# 10_Clock.net
KiCad netlist of a schematic drawn in Altium Designer
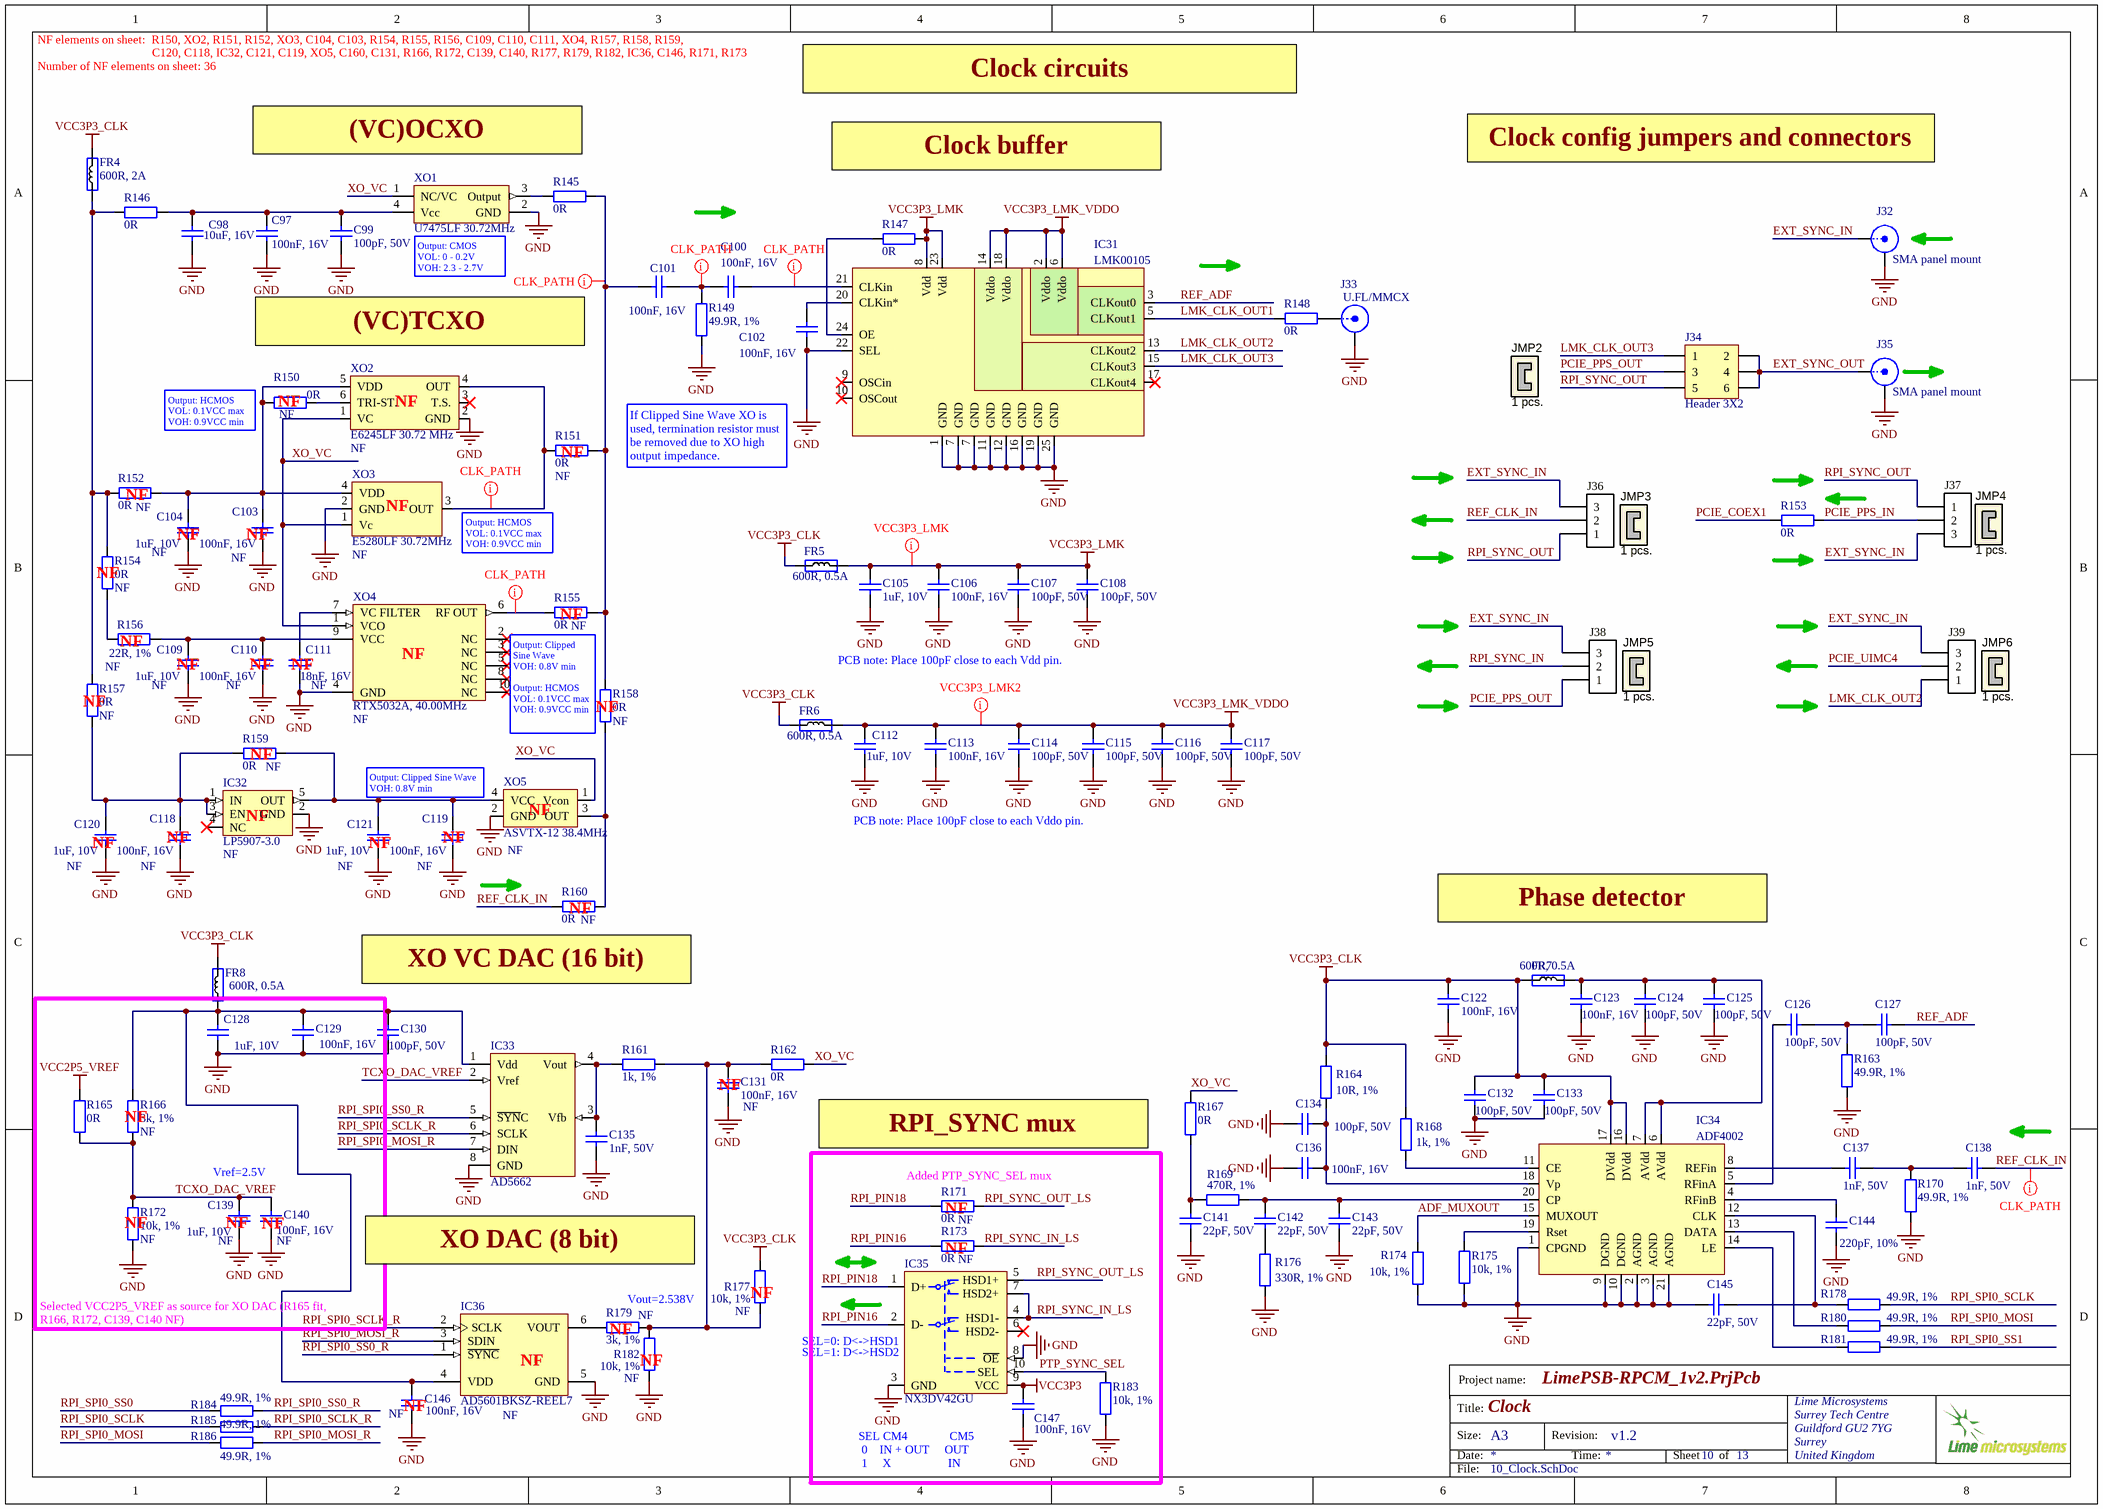
[diagram p0: 10_Clock.SchDoc]

(export (version "E")
  (design (tool "Eeschema 10.0.6"))
  (components
    (comp (ref "C97")
      (value "100nF, 16V")
      (footprint "CAP0402")
      (fields
        (field (name "MANUFACTURER") "Murata Electronics")
        (field (name "TOLERANCE") "10 %")
        (field (name "MANUFACTURER PART NUMBER") "GRM155R71C104KA88D")
      )
      (libsource (lib "LimeMicroAltiumLib_schLib") (part "Cap_0402"))
    )
    (comp (ref "C98")
      (value "10uF, 16V")
      (footprint "CAP0603")
      (fields (field (name "MANUFACTURER") "Yageo") (field (name "TOLERANCE") "±20%"))
      (libsource (lib "LimeMicroAltiumLib_schLib") (part "Cap_0603"))
    )
    (comp (ref "C99")
      (value "100pF, 50V")
      (footprint "CAP0402")
      (fields (field (name "TOLERANCE") "±5%") (field (name "MANUFACTURER") "Yageo"))
      (libsource (lib "LimeMicroAltiumLib_schLib") (part "Cap_0402"))
    )
    (comp (ref "C100")
      (value "100nF, 16V")
      (footprint "CAP0402")
      (fields
        (field (name "MANUFACTURER") "Murata Electronics")
        (field (name "TOLERANCE") "10 %")
        (field (name "MANUFACTURER PART NUMBER") "GRM155R71C104KA88D")
      )
      (libsource (lib "LimeMicroAltiumLib_schLib") (part "Cap_0402"))
    )
    (comp (ref "C101")
      (value "100nF, 16V")
      (footprint "CAP0402")
      (fields
        (field (name "MANUFACTURER") "Murata Electronics")
        (field (name "TOLERANCE") "10 %")
        (field (name "MANUFACTURER PART NUMBER") "GRM155R71C104KA88D")
      )
      (libsource (lib "LimeMicroAltiumLib_schLib") (part "Cap_0402"))
    )
    (comp (ref "C102")
      (value "100nF, 16V")
      (footprint "CAP0402")
      (fields
        (field (name "MANUFACTURER") "Murata Electronics")
        (field (name "TOLERANCE") "10 %")
        (field (name "MANUFACTURER PART NUMBER") "GRM155R71C104KA88D")
      )
      (libsource (lib "LimeMicroAltiumLib_schLib") (part "Cap_0402"))
    )
    (comp (ref "C103")
      (value "100nF, 16V")
      (footprint "CAP0402")
      (fields
        (field (name "ASSEMBLY INFO") "NF")
        (field (name "MANUFACTURER") "Murata Electronics")
        (field (name "TOLERANCE") "10 %")
        (field (name "MANUFACTURER PART NUMBER") "GRM155R71C104KA88D")
      )
      (libsource (lib "LimeMicroAltiumLib_schLib") (part "Cap_0402"))
    )
    (comp (ref "C104")
      (value "1uF, 10V")
      (footprint "CAP0402")
      (description "CAP CER 1UF 10V X5R 0402")
      (fields (field (name "ASSEMBLY INFO") "NF") (field (name "MANUFACTURER") "Yageo"))
      (libsource (lib "LimeMicroAltiumLib_schLib") (part "Cap_0402"))
    )
    (comp (ref "C105")
      (value "1uF, 10V")
      (footprint "CAP0402")
      (description "CAP CER 1UF 10V X5R 0402")
      (fields (field (name "MANUFACTURER") "Yageo") (field (name "TOLERANCE") "±20%"))
      (libsource (lib "LimeMicroAltiumLib_schLib") (part "Cap_0402"))
    )
    (comp (ref "C106")
      (value "100nF, 16V")
      (footprint "CAP0402")
      (fields
        (field (name "MANUFACTURER") "Murata Electronics")
        (field (name "TOLERANCE") "10 %")
        (field (name "MANUFACTURER PART NUMBER") "GRM155R71C104KA88D")
      )
      (libsource (lib "LimeMicroAltiumLib_schLib") (part "Cap_0402"))
    )
    (comp (ref "C107")
      (value "100pF, 50V")
      (footprint "CAP0402")
      (fields (field (name "MANUFACTURER") "Yageo") (field (name "TOLERANCE") "±5%"))
      (libsource (lib "LimeMicroAltiumLib_schLib") (part "Cap_0402"))
    )
    (comp (ref "C108")
      (value "100pF, 50V")
      (footprint "CAP0402")
      (fields (field (name "MANUFACTURER") "Yageo") (field (name "TOLERANCE") "±5%"))
      (libsource (lib "LimeMicroAltiumLib_schLib") (part "Cap_0402"))
    )
    (comp (ref "C109")
      (value "1uF, 10V")
      (footprint "CAP0402")
      (description "CAP CER 1UF 10V X5R 0402")
      (fields (field (name "ASSEMBLY INFO") "NF") (field (name "MANUFACTURER") "Yageo"))
      (libsource (lib "LimeMicroAltiumLib_schLib") (part "Cap_0402"))
    )
    (comp (ref "C110")
      (value "100nF, 16V")
      (footprint "CAP0402")
      (fields
        (field (name "ASSEMBLY INFO") "NF")
        (field (name "MANUFACTURER") "Murata Electronics")
        (field (name "TOLERANCE") "10 %")
        (field (name "MANUFACTURER PART NUMBER") "GRM155R71C104KA88D")
      )
      (libsource (lib "LimeMicroAltiumLib_schLib") (part "Cap_0402"))
    )
    (comp (ref "C111")
      (value "18nF, 16V")
      (footprint "CAP0402")
      (fields
        (field (name "ASSEMBLY INFO") "NF")
        (field (name "MANUFACTURER") "Yageo")
        (field (name "TOLERANCE") "±10%")
      )
      (libsource (lib "LimeMicroAltiumLib_schLib") (part "Cap_0402"))
    )
    (comp (ref "C112")
      (value "1uF, 10V")
      (footprint "CAP0402")
      (description "CAP CER 1UF 10V X5R 0402")
      (fields (field (name "MANUFACTURER") "Yageo") (field (name "TOLERANCE") "±20%"))
      (libsource (lib "LimeMicroAltiumLib_schLib") (part "Cap_0402"))
    )
    (comp (ref "C113")
      (value "100nF, 16V")
      (footprint "CAP0402")
      (fields
        (field (name "MANUFACTURER") "Murata Electronics")
        (field (name "TOLERANCE") "10 %")
        (field (name "MANUFACTURER PART NUMBER") "GRM155R71C104KA88D")
      )
      (libsource (lib "LimeMicroAltiumLib_schLib") (part "Cap_0402"))
    )
    (comp (ref "C114")
      (value "100pF, 50V")
      (footprint "CAP0402")
      (fields (field (name "MANUFACTURER") "Yageo") (field (name "TOLERANCE") "±5%"))
      (libsource (lib "LimeMicroAltiumLib_schLib") (part "Cap_0402"))
    )
    (comp (ref "C115")
      (value "100pF, 50V")
      (footprint "CAP0402")
      (fields (field (name "MANUFACTURER") "Yageo") (field (name "TOLERANCE") "±5%"))
      (libsource (lib "LimeMicroAltiumLib_schLib") (part "Cap_0402"))
    )
    (comp (ref "C116")
      (value "100pF, 50V")
      (footprint "CAP0402")
      (fields (field (name "MANUFACTURER") "Yageo") (field (name "TOLERANCE") "±5%"))
      (libsource (lib "LimeMicroAltiumLib_schLib") (part "Cap_0402"))
    )
    (comp (ref "C117")
      (value "100pF, 50V")
      (footprint "CAP0402")
      (fields (field (name "MANUFACTURER") "Yageo") (field (name "TOLERANCE") "±5%"))
      (libsource (lib "LimeMicroAltiumLib_schLib") (part "Cap_0402"))
    )
    (comp (ref "C118")
      (value "100nF, 16V")
      (footprint "CAP0402")
      (fields
        (field (name "ASSEMBLY INFO") "NF")
        (field (name "MANUFACTURER") "Murata Electronics")
        (field (name "TOLERANCE") "10 %")
        (field (name "MANUFACTURER PART NUMBER") "GRM155R71C104KA88D")
      )
      (libsource (lib "") (part "Cap_0402_1"))
    )
    (comp (ref "C119")
      (value "100nF, 16V")
      (footprint "CAP0402")
      (fields
        (field (name "ASSEMBLY INFO") "NF")
        (field (name "MANUFACTURER") "Murata Electronics")
        (field (name "TOLERANCE") "10 %")
        (field (name "MANUFACTURER PART NUMBER") "GRM155R71C104KA88D")
      )
      (libsource (lib "") (part "Cap_0402_1"))
    )
    (comp (ref "C120")
      (value "1uF, 10V")
      (footprint "CAP0402")
      (fields (field (name "ASSEMBLY INFO") "NF") (field (name "MANUFACTURER") "Yageo"))
      (libsource (lib "") (part "Cap_0402_1"))
    )
    (comp (ref "C121")
      (value "1uF, 10V")
      (footprint "CAP0402")
      (fields (field (name "ASSEMBLY INFO") "NF") (field (name "MANUFACTURER") "Yageo"))
      (libsource (lib "") (part "Cap_0402_1"))
    )
    (comp (ref "C122")
      (value "100nF, 16V")
      (footprint "CAP0402")
      (fields
        (field (name "MANUFACTURER") "Murata Electronics")
        (field (name "TOLERANCE") "10 %")
        (field (name "MANUFACTURER PART NUMBER") "GRM155R71C104KA88D")
      )
      (libsource (lib "LimeMicroAltiumLib_schLib") (part "Cap_0402"))
    )
    (comp (ref "C123")
      (value "100nF, 16V")
      (footprint "CAP0402")
      (fields
        (field (name "MANUFACTURER") "Murata Electronics")
        (field (name "TOLERANCE") "10 %")
        (field (name "MANUFACTURER PART NUMBER") "GRM155R71C104KA88D")
      )
      (libsource (lib "LimeMicroAltiumLib_schLib") (part "Cap_0402"))
    )
    (comp (ref "C124")
      (value "100pF, 50V")
      (footprint "CAP0402")
      (fields (field (name "MANUFACTURER") "Yageo") (field (name "TOLERANCE") "±5%"))
      (libsource (lib "LimeMicroAltiumLib_schLib") (part "Cap_0402"))
    )
    (comp (ref "C125")
      (value "100pF, 50V")
      (footprint "CAP0402")
      (fields (field (name "MANUFACTURER") "Yageo") (field (name "TOLERANCE") "±5%"))
      (libsource (lib "LimeMicroAltiumLib_schLib") (part "Cap_0402"))
    )
    (comp (ref "C126")
      (value "100pF, 50V")
      (footprint "CAP0402")
      (fields (field (name "MANUFACTURER") "Yageo") (field (name "TOLERANCE") "±5%"))
      (libsource (lib "LimeMicroAltiumLib_schLib") (part "Cap_0402"))
    )
    (comp (ref "C127")
      (value "100pF, 50V")
      (footprint "CAP0402")
      (fields (field (name "MANUFACTURER") "Yageo") (field (name "TOLERANCE") "±5%"))
      (libsource (lib "LimeMicroAltiumLib_schLib") (part "Cap_0402"))
    )
    (comp (ref "C128")
      (value "1uF, 10V")
      (footprint "CAP0402")
      (description "CAP CER 1UF 10V X5R 0402")
      (fields (field (name "MANUFACTURER") "Yageo") (field (name "TOLERANCE") "±20%"))
      (libsource (lib "LimeMicroAltiumLib_schLib") (part "Cap_0402"))
    )
    (comp (ref "C129")
      (value "100nF, 16V")
      (footprint "CAP0402")
      (fields
        (field (name "TOLERANCE") "10 %")
        (field (name "MANUFACTURER") "Murata Electronics")
        (field (name "MANUFACTURER PART NUMBER") "GRM155R71C104KA88D")
      )
      (libsource (lib "LimeFPGAboard_schLib") (part "Cap_0603"))
    )
    (comp (ref "C130")
      (value "100pF, 50V")
      (footprint "CAP0402")
      (fields (field (name "MANUFACTURER") "Yageo") (field (name "TOLERANCE") "±5%"))
      (libsource (lib "LimeMicroAltiumLib_schLib") (part "Cap_0402"))
    )
    (comp (ref "C131")
      (value "100nF, 16V")
      (footprint "CAP0402")
      (fields
        (field (name "ASSEMBLY INFO") "NF")
        (field (name "MANUFACTURER") "Murata Electronics")
        (field (name "TOLERANCE") "10 %")
        (field (name "MANUFACTURER PART NUMBER") "GRM155R71C104KA88D")
      )
      (libsource (lib "LimeMicroAltiumLib_schLib") (part "Cap_0402"))
    )
    (comp (ref "C132")
      (value "100pF, 50V")
      (footprint "CAP0402")
      (fields (field (name "MANUFACTURER") "Yageo") (field (name "TOLERANCE") "±5%"))
      (libsource (lib "LimeMicroAltiumLib_schLib") (part "Cap_0402"))
    )
    (comp (ref "C133")
      (value "100pF, 50V")
      (footprint "CAP0402")
      (fields (field (name "MANUFACTURER") "Yageo") (field (name "TOLERANCE") "±5%"))
      (libsource (lib "LimeMicroAltiumLib_schLib") (part "Cap_0402"))
    )
    (comp (ref "C134")
      (value "100pF, 50V")
      (footprint "CAP0402")
      (fields (field (name "MANUFACTURER") "Yageo") (field (name "TOLERANCE") "±5%"))
      (libsource (lib "LimeMicroAltiumLib_schLib") (part "Cap_0402"))
    )
    (comp (ref "C135")
      (value "1nF, 50V")
      (footprint "CAP0402")
      (fields
        (field (name "TOLERANCE") "±10%")
        (field (name "MANUFACTURER") "Murata Electronics North America")
      )
      (libsource (lib "LimeMicroAltiumLib_schLib") (part "Cap_0402"))
    )
    (comp (ref "C136")
      (value "100nF, 16V")
      (footprint "CAP0402")
      (fields
        (field (name "MANUFACTURER") "Murata Electronics")
        (field (name "TOLERANCE") "10 %")
        (field (name "MANUFACTURER PART NUMBER") "GRM155R71C104KA88D")
      )
      (libsource (lib "LimeMicroAltiumLib_schLib") (part "Cap_0402"))
    )
    (comp (ref "C137")
      (value "1nF, 50V")
      (footprint "CAP0402")
      (fields
        (field (name "TOLERANCE") "±10%")
        (field (name "MANUFACTURER") "Murata Electronics North America")
      )
      (libsource (lib "LimeMicroAltiumLib_schLib") (part "Cap_0402"))
    )
    (comp (ref "C138")
      (value "1nF, 50V")
      (footprint "CAP0402")
      (fields
        (field (name "TOLERANCE") "±10%")
        (field (name "MANUFACTURER") "Murata Electronics North America")
      )
      (libsource (lib "LimeMicroAltiumLib_schLib") (part "Cap_0402"))
    )
    (comp (ref "C139")
      (value "1uF, 10V")
      (footprint "CAP0402")
      (description "CAP CER 1UF 10V X5R 0402")
      (fields
        (field (name "ASSEMBLY INFO") "NF")
        (field (name "MANUFACTURER") "Yageo")
        (field (name "TOLERANCE") "±20%")
      )
      (libsource (lib "LimeMicroAltiumLib_schLib") (part "Cap_0402"))
    )
    (comp (ref "C140")
      (value "100nF, 16V")
      (footprint "CAP0402")
      (fields
        (field (name "TOLERANCE") "10 %")
        (field (name "MANUFACTURER") "Murata Electronics")
        (field (name "MANUFACTURER PART NUMBER") "GRM155R71C104KA88D")
        (field (name "ASSEMBLY INFO") "NF")
      )
      (libsource (lib "LimeFPGAboard_schLib") (part "Cap_0603"))
    )
    (comp (ref "C141")
      (value "22pF, 50V")
      (footprint "CAP0402")
      (fields (field (name "TOLERANCE") "±5%") (field (name "MANUFACTURER") "Yageo"))
      (libsource (lib "LimeMicroAltiumLib_schLib") (part "Cap_0402"))
    )
    (comp (ref "C142")
      (value "22pF, 50V")
      (footprint "CAP0402")
      (fields (field (name "TOLERANCE") "±5%") (field (name "MANUFACTURER") "Yageo"))
      (libsource (lib "LimeMicroAltiumLib_schLib") (part "Cap_0402"))
    )
    (comp (ref "C143")
      (value "22pF, 50V")
      (footprint "CAP0402")
      (fields (field (name "TOLERANCE") "±5%") (field (name "MANUFACTURER") "Yageo"))
      (libsource (lib "LimeMicroAltiumLib_schLib") (part "Cap_0402"))
    )
    (comp (ref "C144")
      (value "220pF, 10%")
      (footprint "CAP0402")
      (fields (field (name "MANUFACTURER") "Yageo") (field (name "TOLERANCE") "±10%"))
      (libsource (lib "LimeMicroAltiumLib_schLib") (part "Cap_0402"))
    )
    (comp (ref "C145")
      (value "22pF, 50V")
      (footprint "CAP0402")
      (fields (field (name "TOLERANCE") "±5%") (field (name "MANUFACTURER") "Yageo"))
      (libsource (lib "LimeMicroAltiumLib_schLib") (part "Cap_0402"))
    )
    (comp (ref "C146")
      (value "100nF, 16V")
      (footprint "CAP0402")
      (fields
        (field (name "TOLERANCE") "10 %")
        (field (name "MANUFACTURER") "Murata Electronics")
        (field (name "MANUFACTURER PART NUMBER") "GRM155R71C104KA88D")
        (field (name "ASSEMBLY INFO") "NF")
      )
      (libsource (lib "LimeFPGAboard_schLib") (part "Cap_0603"))
    )
    (comp (ref "C147")
      (value "100nF, 16V")
      (footprint "CAP0402")
      (fields
        (field (name "MANUFACTURER") "Murata Electronics")
        (field (name "TOLERANCE") "10 %")
        (field (name "MANUFACTURER PART NUMBER") "GRM155R71C104KA88D")
      )
      (libsource (lib "LimeMicroAltiumLib_schLib") (part "Cap_0402"))
    )
    (comp (ref "FR4")
      (value "600R, 2A")
      (footprint "RES0805")
      (fields (field (name "MANUFACTURER") "TDK Corporation"))
      (libsource (lib "LimeFPGAboard_schLib") (part "Ferrite"))
    )
    (comp (ref "FR5")
      (value "600R, 0.5A")
      (footprint "RES0402")
      (fields (field (name "MANUFACTURER") "Murata") (field (name "TOLERANCE") "25%"))
      (libsource (lib "LimeMicroAltiumLib_schLib") (part "Ferrite"))
    )
    (comp (ref "FR6")
      (value "600R, 0.5A")
      (footprint "RES0402")
      (fields (field (name "MANUFACTURER") "Murata") (field (name "TOLERANCE") "25%"))
      (libsource (lib "LimeMicroAltiumLib_schLib") (part "Ferrite"))
    )
    (comp (ref "FR7")
      (value "600R, 0.5A")
      (footprint "RES0402")
      (fields (field (name "MANUFACTURER") "Murata") (field (name "TOLERANCE") "25%"))
      (libsource (lib "LimeMicroAltiumLib_schLib") (part "Ferrite"))
    )
    (comp (ref "FR8")
      (value "600R, 0.5A")
      (footprint "RES0402")
      (fields (field (name "MANUFACTURER") "Murata") (field (name "TOLERANCE") "25%"))
      (libsource (lib "LimeMicroAltiumLib_schLib") (part "Ferrite"))
    )
    (comp (ref "IC31")
      (value "LMK00105")
      (footprint "LMK00105SQ")
      (fields (field (name "MANUFACTURER") "Texas Instruments"))
      (libsource (lib "LimeMicroAltiumLib_schLib") (part "LMK00105"))
    )
    (comp (ref "IC32")
      (value "LP5907-3.0")
      (footprint "SOT23-5")
      (fields (field (name "MANUFACTURER") "Texas Instruments") (field (name "ASSEMBLY INFO") "NF"))
      (libsource (lib "LimeMicroAltiumLib_schLib_r01") (part "LP5907"))
    )
    (comp (ref "IC33")
      (value "AD5662")
      (footprint "AD5662_SOT23-8")
      (fields (field (name "MANUFACTURER") "Analog Devices Inc."))
      (libsource (lib "LimeMicroAltiumLib_schLib") (part "AD5662"))
    )
    (comp (ref "IC34")
      (value "ADF4002")
      (footprint "ADF4002")
      (fields (field (name "MANUFACTURER") "Analog Devices Inc"))
      (libsource (lib "LimeMicroAltiumLib_schLib") (part "ADF4002"))
    )
    (comp (ref "IC35")
      (value "NX3DV42GU")
      (footprint "FSUSB42UMX")
      (fields (field (name "MANUFACTURER") "NXP Semiconductors"))
      (libsource (lib "LimeMicroAltiumLib_schLib_r01") (part "FSUSB42UMX"))
    )
    (comp (ref "IC36")
      (value "AD5601BKSZ-REEL7")
      (footprint "AD5601_SOT23-6")
      (fields
        (field (name "GENERIC PART NUMBER") "AD5601")
        (field (name "MANUFACTURER") "Analog Devices")
        (field (name "ASSEMBLY INFO") "NF")
      )
      (libsource (lib "LimeMicroAltiumLib_schLib") (part "AD5601BKSZ-REEL7"))
    )
    (comp (ref "J32")
      (value "SMA panel mount")
      (footprint "SMA_connector_side")
      (description "CONN SMA JACK STR 50OHM EDGE MNT")
      (fields (field (name "MANUFACTURER") "Linx"))
      (libsource (lib "") (part "RF_IF_connector_1"))
    )
    (comp (ref "J33")
      (value "U.FL/MMCX")
      (footprint "MMCX_UFL_conn_u")
      (description "CONN UMC RCPT STR 50 OHM SMD")
      (fields (field (name "MANUFACTURER") "Molex, LLC"))
      (libsource (lib "LimeMicroAltiumLib_schLib") (part "RF_IF_connector"))
    )
    (comp (ref "J34")
      (value "Header 3X2")
      (footprint "Header3x2")
      (description "Header, 2-Pin, Dual row")
      (fields
        (field (name "MANUFACTURER PART NUMBER") "PH2-06-UA")
        (field (name "MANUFACTURER") "Adam Equipment")
      )
      (libsource (lib "LimeMicroAltiumLib_schLib_r01") (part "Header 3X2"))
    )
    (comp (ref "J35")
      (value "SMA panel mount")
      (footprint "SMA_connector_side")
      (description "CONN SMA JACK STR 50OHM EDGE MNT")
      (fields (field (name "MANUFACTURER") "Linx"))
      (libsource (lib "") (part "RF_IF_connector_1"))
    )
    (comp (ref "J36")
      (value "Header 3x1 pin")
      (footprint "HDR_1x3")
      (description "Header, 3-pin")
      (fields
        (field (name "MANUFACTURER PART NUMBER") "61300311121")
        (field (name "MANUFACTURER") "Wurth Electronics")
      )
      (libsource (lib "LimeMicroAltiumLib_schLib_r04") (part "Header3P"))
    )
    (comp (ref "J37")
      (value "Header 3x1 pin")
      (footprint "HDR_1x3")
      (description "Header, 3-pin")
      (fields
        (field (name "MANUFACTURER PART NUMBER") "61300311121")
        (field (name "MANUFACTURER") "Wurth Electronics")
      )
      (libsource (lib "") (part "Header3P_1"))
    )
    (comp (ref "J38")
      (value "Header 3x1 pin")
      (footprint "HDR_1x3")
      (description "Header, 3-pin")
      (fields
        (field (name "MANUFACTURER PART NUMBER") "61300311121")
        (field (name "MANUFACTURER") "Wurth Electronics")
      )
      (libsource (lib "LimeMicroAltiumLib_schLib_r04") (part "Header3P"))
    )
    (comp (ref "J39")
      (value "Header 3x1 pin")
      (footprint "HDR_1x3")
      (description "Header, 3-pin")
      (fields
        (field (name "MANUFACTURER PART NUMBER") "61300311121")
        (field (name "MANUFACTURER") "Wurth Electronics")
      )
      (libsource (lib "LimeMicroAltiumLib_schLib_r04") (part "Header3P"))
    )
    (comp (ref "JMP2")
      (value "1 pcs.")
      (description "Shorting Jumper, 2-position, 1.27mm pitch")
      (fields (field (name "MANUFACTURER") "Sullins"))
      (libsource (lib "LimeMicroAltiumLib_schLib") (part "JUMP_2P_CONN_HEADER"))
    )
    (comp (ref "JMP3")
      (value "1 pcs.")
      (description "Shorting Jumper, 2-position, 1.27mm pitch")
      (fields (field (name "MANUFACTURER") "Sullins"))
      (libsource (lib "LimeMicroAltiumLib_schLib") (part "JUMP_2P_CONN_HEADER"))
    )
    (comp (ref "JMP4")
      (value "1 pcs.")
      (description "Shorting Jumper, 2-position, 1.27mm pitch")
      (fields (field (name "MANUFACTURER") "Sullins"))
      (libsource (lib "LimeMicroAltiumLib_schLib") (part "JUMP_2P_CONN_HEADER"))
    )
    (comp (ref "JMP5")
      (value "1 pcs.")
      (description "Shorting Jumper, 2-position, 1.27mm pitch")
      (fields (field (name "MANUFACTURER") "Sullins"))
      (libsource (lib "LimeMicroAltiumLib_schLib") (part "JUMP_2P_CONN_HEADER"))
    )
    (comp (ref "JMP6")
      (value "1 pcs.")
      (description "Shorting Jumper, 2-position, 1.27mm pitch")
      (fields (field (name "MANUFACTURER") "Sullins"))
      (libsource (lib "LimeMicroAltiumLib_schLib") (part "JUMP_2P_CONN_HEADER"))
    )
    (comp (ref "R145")
      (value "0R")
      (footprint "RES0402_v2")
      (fields (field (name "MANUFACTURER") "Yageo") (field (name "TOLERANCE") "Jumper"))
      (libsource (lib "LimeMicroAltiumLib_schLib") (part "Res_0402"))
    )
    (comp (ref "R146")
      (value "0R")
      (footprint "RES0402")
      (fields (field (name "MANUFACTURER") "Yageo") (field (name "TOLERANCE") "Jumper"))
      (libsource (lib "LimeMicroAltiumLib_schLib") (part "Res_0402"))
    )
    (comp (ref "R147")
      (value "0R")
      (footprint "RES0402")
      (fields (field (name "MANUFACTURER") "Yageo") (field (name "TOLERANCE") "Jumper"))
      (libsource (lib "LimeMicroAltiumLib_schLib") (part "Res_0402"))
    )
    (comp (ref "R148")
      (value "0R")
      (footprint "RES0402")
      (fields (field (name "MANUFACTURER") "Yageo") (field (name "TOLERANCE") "Jumper"))
      (libsource (lib "") (part "Res_0402_1"))
    )
    (comp (ref "R149")
      (value "49.9R, 1%")
      (footprint "RES0402")
      (fields
        (field (name "TOLERANCE") "±1%")
        (field (name "MANUFACTURER") "Samsung Electro-Mechanics America, Inc.")
      )
      (libsource (lib "LimeMicroAltiumLib_schLib") (part "Res_0402"))
    )
    (comp (ref "R150")
      (value "0R")
      (footprint "RES0402")
      (fields
        (field (name "ASSEMBLY INFO") "NF")
        (field (name "MANUFACTURER") "Yageo")
        (field (name "TOLERANCE") "Jumper")
      )
      (libsource (lib "LimeMicroAltiumLib_schLib") (part "Res_0402"))
    )
    (comp (ref "R151")
      (value "0R")
      (footprint "RES0402_v2")
      (fields
        (field (name "ASSEMBLY INFO") "NF")
        (field (name "MANUFACTURER") "Yageo")
        (field (name "TOLERANCE") "Jumper")
      )
      (libsource (lib "LimeMicroAltiumLib_schLib") (part "Res_0402"))
    )
    (comp (ref "R152")
      (value "0R")
      (footprint "RES0402")
      (fields
        (field (name "MANUFACTURER") "Yageo")
        (field (name "TOLERANCE") "Jumper")
        (field (name "ASSEMBLY INFO") "NF")
      )
      (libsource (lib "LimeMicroAltiumLib_schLib") (part "Res_0402"))
    )
    (comp (ref "R153")
      (value "0R")
      (footprint "RES0402")
      (fields (field (name "MANUFACTURER") "Yageo") (field (name "TOLERANCE") "Jumper"))
      (libsource (lib "") (part "Res_0402_1"))
    )
    (comp (ref "R154")
      (value "0R")
      (footprint "RES0402")
      (fields
        (field (name "ASSEMBLY INFO") "NF")
        (field (name "MANUFACTURER") "Yageo")
        (field (name "TOLERANCE") "Jumper")
      )
      (libsource (lib "LimeMicroAltiumLib_schLib") (part "Res_0402"))
    )
    (comp (ref "R155")
      (value "0R")
      (footprint "RES0402_v2")
      (fields
        (field (name "ASSEMBLY INFO") "NF")
        (field (name "MANUFACTURER") "Yageo")
        (field (name "TOLERANCE") "Jumper")
      )
      (libsource (lib "LimeMicroAltiumLib_schLib") (part "Res_0402"))
    )
    (comp (ref "R156")
      (value "22R, 1%")
      (footprint "RES0402")
      (fields
        (field (name "TOLERANCE") "±1%")
        (field (name "MANUFACTURER") "Yageo")
        (field (name "ASSEMBLY INFO") "NF")
      )
      (libsource (lib "LimeFPGAboard_schLib") (part "Res_0402"))
    )
    (comp (ref "R157")
      (value "0R")
      (footprint "RES0402")
      (fields
        (field (name "MANUFACTURER") "Yageo")
        (field (name "TOLERANCE") "Jumper")
        (field (name "ASSEMBLY INFO") "NF")
      )
      (libsource (lib "") (part "Res_0402_1"))
    )
    (comp (ref "R158")
      (value "0R")
      (footprint "RES0402_v2")
      (fields
        (field (name "ASSEMBLY INFO") "NF")
        (field (name "MANUFACTURER") "Yageo")
        (field (name "TOLERANCE") "Jumper")
      )
      (libsource (lib "") (part "Res_0402_1"))
    )
    (comp (ref "R159")
      (value "0R")
      (footprint "RES0402")
      (fields
        (field (name "MANUFACTURER") "Yageo")
        (field (name "TOLERANCE") "Jumper")
        (field (name "ASSEMBLY INFO") "NF")
      )
      (libsource (lib "") (part "Res_0402_1"))
    )
    (comp (ref "R160")
      (value "0R")
      (footprint "RES0402_v2")
      (fields
        (field (name "ASSEMBLY INFO") "NF")
        (field (name "MANUFACTURER") "Yageo")
        (field (name "TOLERANCE") "Jumper")
      )
      (libsource (lib "LimeMicroAltiumLib_schLib") (part "Res_0402"))
    )
    (comp (ref "R161")
      (value "1k, 1%")
      (footprint "RES0402")
      (fields (field (name "MANUFACTURER") "Stackpole Electronics Inc") (field (name "TOLERANCE") "±1%"))
      (libsource (lib "LimeMicroAltiumLib_schLib") (part "Res_0402"))
    )
    (comp (ref "R162")
      (value "0R")
      (footprint "RES0402")
      (fields (field (name "MANUFACTURER") "Yageo") (field (name "TOLERANCE") "Jumper"))
      (libsource (lib "LimeMicroAltiumLib_schLib") (part "Res_0402"))
    )
    (comp (ref "R163")
      (value "49.9R, 1%")
      (footprint "RES0402")
      (fields
        (field (name "TOLERANCE") "±1%")
        (field (name "MANUFACTURER") "Samsung Electro-Mechanics America, Inc.")
      )
      (libsource (lib "LimeMicroAltiumLib_schLib") (part "Res_0402"))
    )
    (comp (ref "R164")
      (value "10R, 1%")
      (footprint "RES0402")
      (fields (field (name "MANUFACTURER") "Stackpole Electronics") (field (name "TOLERANCE") "1%"))
      (libsource (lib "LimeMicroAltiumLib_schLib") (part "Res_0402"))
    )
    (comp (ref "R165")
      (value "0R")
      (footprint "RES0402_v2")
      (fields (field (name "MANUFACTURER") "Yageo") (field (name "TOLERANCE") "Jumper"))
      (libsource (lib "LimeMicroAltiumLib_schLib") (part "Res_0402"))
    )
    (comp (ref "R166")
      (value "3k, 1%")
      (footprint "RES0402")
      (fields
        (field (name "ASSEMBLY INFO") "NF")
        (field (name "TOLERANCE") "±1%")
        (field (name "MANUFACTURER") "Vishay Dale")
      )
      (libsource (lib "LimeMicroAltiumLib_schLib") (part "Res_0402"))
    )
    (comp (ref "R167")
      (value "0R")
      (footprint "RES0402")
      (fields (field (name "MANUFACTURER") "Yageo") (field (name "TOLERANCE") "Jumper"))
      (libsource (lib "LimeMicroAltiumLib_schLib") (part "Res_0402"))
    )
    (comp (ref "R168")
      (value "1k, 1%")
      (footprint "RES0402")
      (fields (field (name "MANUFACTURER") "Stackpole Electronics Inc") (field (name "TOLERANCE") "±1%"))
      (libsource (lib "LimeMicroAltiumLib_schLib") (part "Res_0402"))
    )
    (comp (ref "R169")
      (value "470R, 1%")
      (footprint "RES0402")
      (fields (field (name "TOLERANCE") "1%") (field (name "MANUFACTURER") "Yageo"))
      (libsource (lib "") (part "Res_0402_1"))
    )
    (comp (ref "R170")
      (value "49.9R, 1%")
      (footprint "RES0402")
      (fields
        (field (name "TOLERANCE") "±1%")
        (field (name "MANUFACTURER") "Samsung Electro-Mechanics America, Inc.")
      )
      (libsource (lib "LimeMicroAltiumLib_schLib") (part "Res_0402"))
    )
    (comp (ref "R171")
      (value "0R")
      (footprint "RES0402")
      (fields
        (field (name "ASSEMBLY INFO") "NF")
        (field (name "MANUFACTURER") "Yageo")
        (field (name "TOLERANCE") "Jumper")
      )
      (libsource (lib "") (part "Res_0402_1"))
    )
    (comp (ref "R172")
      (value "10k, 1%")
      (footprint "RES0402")
      (fields
        (field (name "ASSEMBLY INFO") "NF")
        (field (name "MANUFACTURER") "Yageo")
        (field (name "TOLERANCE") "±1%")
      )
      (libsource (lib "LimeMicroAltiumLib_schLib") (part "Res_0402"))
    )
    (comp (ref "R173")
      (value "0R")
      (footprint "RES0402")
      (fields
        (field (name "ASSEMBLY INFO") "NF")
        (field (name "MANUFACTURER") "Yageo")
        (field (name "TOLERANCE") "Jumper")
      )
      (libsource (lib "") (part "Res_0402_1"))
    )
    (comp (ref "R174")
      (value "10k, 1%")
      (footprint "RES0402")
      (fields (field (name "MANUFACTURER") "Yageo") (field (name "TOLERANCE") "±1%"))
      (libsource (lib "LimeMicroAltiumLib_schLib") (part "Res_0402"))
    )
    (comp (ref "R175")
      (value "10k, 1%")
      (footprint "RES0402")
      (fields (field (name "MANUFACTURER") "Yageo") (field (name "TOLERANCE") "±1%"))
      (libsource (lib "LimeMicroAltiumLib_schLib") (part "Res_0402"))
    )
    (comp (ref "R176")
      (value "330R, 1%")
      (footprint "RES0402")
      (fields (field (name "MANUFACTURER") "Yageo") (field (name "TOLERANCE") "1%"))
      (libsource (lib "LimeMicroAltiumLib_schLib") (part "Res_0402"))
    )
    (comp (ref "R177")
      (value "10k, 1%")
      (footprint "RES0402")
      (fields
        (field (name "ASSEMBLY INFO") "NF")
        (field (name "MANUFACTURER") "Yageo")
        (field (name "TOLERANCE") "±1%")
      )
      (libsource (lib "LimeMicroAltiumLib_schLib") (part "Res_0402"))
    )
    (comp (ref "R178")
      (value "49.9R, 1%")
      (footprint "RES0402")
      (fields
        (field (name "TOLERANCE") "±1%")
        (field (name "MANUFACTURER") "Samsung Electro-Mechanics America, Inc.")
      )
      (libsource (lib "LimeMicroAltiumLib_schLib") (part "Res_0402"))
    )
    (comp (ref "R179")
      (value "3k, 1%")
      (footprint "RES0402")
      (fields
        (field (name "ASSEMBLY INFO") "NF")
        (field (name "TOLERANCE") "±1%")
        (field (name "MANUFACTURER") "Vishay Dale")
      )
      (libsource (lib "LimeMicroAltiumLib_schLib") (part "Res_0402"))
    )
    (comp (ref "R180")
      (value "49.9R, 1%")
      (footprint "RES0402")
      (fields
        (field (name "TOLERANCE") "±1%")
        (field (name "MANUFACTURER") "Samsung Electro-Mechanics America, Inc.")
      )
      (libsource (lib "LimeMicroAltiumLib_schLib") (part "Res_0402"))
    )
    (comp (ref "R181")
      (value "49.9R, 1%")
      (footprint "RES0402")
      (fields
        (field (name "TOLERANCE") "±1%")
        (field (name "MANUFACTURER") "Samsung Electro-Mechanics America, Inc.")
      )
      (libsource (lib "LimeMicroAltiumLib_schLib") (part "Res_0402"))
    )
    (comp (ref "R182")
      (value "10k, 1%")
      (footprint "RES0402")
      (fields
        (field (name "ASSEMBLY INFO") "NF")
        (field (name "MANUFACTURER") "Yageo")
        (field (name "TOLERANCE") "±1%")
      )
      (libsource (lib "LimeMicroAltiumLib_schLib") (part "Res_0402"))
    )
    (comp (ref "R183")
      (value "10k, 1%")
      (footprint "RES0402")
      (fields (field (name "MANUFACTURER") "Yageo") (field (name "TOLERANCE") "±1%"))
      (libsource (lib "LimeMicroAltiumLib_schLib") (part "Res_0402"))
    )
    (comp (ref "R184")
      (value "49.9R, 1%")
      (footprint "RES0402")
      (fields
        (field (name "TOLERANCE") "±1%")
        (field (name "MANUFACTURER") "Samsung Electro-Mechanics America, Inc.")
      )
      (libsource (lib "LimeMicroAltiumLib_schLib") (part "Res_0402"))
    )
    (comp (ref "R185")
      (value "49.9R, 1%")
      (footprint "RES0402")
      (fields
        (field (name "TOLERANCE") "±1%")
        (field (name "MANUFACTURER") "Samsung Electro-Mechanics America, Inc.")
      )
      (libsource (lib "LimeMicroAltiumLib_schLib") (part "Res_0402"))
    )
    (comp (ref "R186")
      (value "49.9R, 1%")
      (footprint "RES0402")
      (fields
        (field (name "TOLERANCE") "±1%")
        (field (name "MANUFACTURER") "Samsung Electro-Mechanics America, Inc.")
      )
      (libsource (lib "LimeMicroAltiumLib_schLib") (part "Res_0402"))
    )
    (comp (ref "XO1")
      (value "U7475LF 30.72MHz")
      (footprint "AOCJYR-10.000MHz")
      (fields (field (name "MANUFACTURER") "Rakon"))
      (libsource (lib "LimeMicroAltiumLib_schLib") (part "AOCJYR-10.000MHz"))
    )
    (comp (ref "XO2")
      (value "E6245LF 30.72 MHz")
      (footprint "RAKON_RPT7050A")
      (fields (field (name "ASSEMBLY INFO") "NF") (field (name "MANUFACTURER") "Rakon"))
      (libsource (lib "LimeMicroAltiumLib_schLib") (part "RPT7050A"))
    )
    (comp (ref "XO3")
      (value "E5280LF 30.72MHz")
      (footprint "RAKON_TXCO")
      (fields (field (name "ASSEMBLY INFO") "NF") (field (name "MANUFACTURER") "Rakon"))
      (libsource (lib "LimeMicroAltiumLib_schLib") (part "TXCO"))
    )
    (comp (ref "XO4")
      (value "RTX5032A, 40.00MHz")
      (footprint "RAKON_RTX5032A")
      (fields (field (name "ASSEMBLY INFO") "NF") (field (name "MANUFACTURER") "Rakon"))
      (libsource (lib "LimeMicroAltiumLib_schLib") (part "Rakon_RTX5032A"))
    )
    (comp (ref "XO5")
      (value "ASVTX-12 38.4MHz")
      (footprint "CRYSTAL_4-LCC_2P5x2P0")
      (description "Oscillator Crystal")
      (fields (field (name "MANUFACTURER") "Abracon") (field (name "ASSEMBLY INFO") "NF"))
      (libsource (lib "LimeMicroAltiumLib_schLib_r01") (part "ASVTX-12-A-38.400MHZ-H10-T_CRYSTAL"))
    )
  )
  (nets
    (net (code "1") (name "/ADF_MUXOUT") (class "Default")
      (node (ref "IC34") (pin "15") (pinfunction "MUXOUT_15") (pintype "passive"))
      (node (ref "R174") (pin "1") (pinfunction "1_1") (pintype "passive"))
    )
    (net (code "2") (name "/EXT_SYNC_IN") (class "Default")
      (node (ref "J32") (pin "1") (pinfunction "X_1") (pintype "passive"))
      (node (ref "J36") (pin "3") (pinfunction "3_3") (pintype "passive"))
      (node (ref "J37") (pin "3") (pinfunction "3_3") (pintype "passive"))
      (node (ref "J38") (pin "3") (pinfunction "3_3") (pintype "passive"))
      (node (ref "J39") (pin "3") (pinfunction "3_3") (pintype "passive"))
    )
    (net (code "3") (name "/EXT_SYNC_OUT") (class "Default")
      (node (ref "J34") (pin "2") (pinfunction "2_2") (pintype "passive"))
      (node (ref "J34") (pin "4") (pinfunction "4_4") (pintype "passive"))
      (node (ref "J34") (pin "6") (pinfunction "6_6") (pintype "passive"))
      (node (ref "J35") (pin "1") (pinfunction "X_1") (pintype "passive"))
    )
    (net (code "4") (name "/LMK_CLK_OUT1") (class "Default")
      (node (ref "IC31") (pin "5") (pinfunction "CLKout1_5") (pintype "passive"))
      (node (ref "R148") (pin "2") (pinfunction "2_2") (pintype "passive"))
    )
    (net (code "5") (name "/LMK_CLK_OUT2") (class "Default")
      (node (ref "IC31") (pin "13") (pinfunction "CLKout2_13") (pintype "passive"))
      (node (ref "J39") (pin "1") (pinfunction "1_1") (pintype "passive"))
    )
    (net (code "6") (name "/LMK_CLK_OUT3") (class "Default")
      (node (ref "IC31") (pin "15") (pinfunction "CLKout3_15") (pintype "passive"))
      (node (ref "J34") (pin "1") (pinfunction "1_1") (pintype "passive"))
    )
    (net (code "7") (name "/PCIE_COEX1") (class "Default")
      (node (ref "R153") (pin "2") (pinfunction "2_2") (pintype "passive"))
    )
    (net (code "9") (name "/PCIE_PPS_OUT") (class "Default")
      (node (ref "J34") (pin "3") (pinfunction "3_3") (pintype "passive"))
      (node (ref "J38") (pin "1") (pinfunction "1_1") (pintype "passive"))
    )
    (net (code "10") (name "/PCIE_UIMC4") (class "Default")
      (node (ref "J39") (pin "2") (pinfunction "2_2") (pintype "passive"))
    )
    (net (code "11") (name "/PTP_SYNC_SEL") (class "Default")
      (node (ref "IC35") (pin "10") (pinfunction "SEL_10") (pintype "input"))
      (node (ref "R183") (pin "1") (pinfunction "1_1") (pintype "passive"))
    )
    (net (code "12") (name "/REF_ADF") (class "Default")
      (node (ref "C127") (pin "2") (pinfunction "2_2") (pintype "passive"))
      (node (ref "IC31") (pin "3") (pinfunction "CLKout0_3") (pintype "passive"))
    )
    (net (code "13") (name "/REF_CLK_IN") (class "Default")
      (node (ref "C138") (pin "2") (pinfunction "2_2") (pintype "passive"))
      (node (ref "J36") (pin "2") (pinfunction "2_2") (pintype "passive"))
      (node (ref "R160") (pin "2") (pinfunction "2_2") (pintype "passive"))
    )
    (net (code "14") (name "/RPI_PIN16") (class "Default")
      (node (ref "IC35") (pin "2") (pinfunction "D-_2") (pintype "passive"))
      (node (ref "R173") (pin "2") (pinfunction "2_2") (pintype "passive"))
    )
    (net (code "15") (name "/RPI_PIN18") (class "Default")
      (node (ref "IC35") (pin "1") (pinfunction "D+_1") (pintype "passive"))
      (node (ref "R171") (pin "2") (pinfunction "2_2") (pintype "passive"))
    )
    (net (code "16") (name "/RPI_SPI0_MOSI") (class "Default")
      (node (ref "R180") (pin "1") (pinfunction "1_1") (pintype "passive"))
      (node (ref "R186") (pin "2") (pinfunction "2_2") (pintype "passive"))
    )
    (net (code "17") (name "/RPI_SPI0_MOSI_R") (class "Default")
      (node (ref "IC33") (pin "7") (pinfunction "DIN_7") (pintype "input"))
      (node (ref "IC36") (pin "3") (pinfunction "SDIN_3") (pintype "input"))
      (node (ref "R186") (pin "1") (pinfunction "1_1") (pintype "passive"))
    )
    (net (code "18") (name "/RPI_SPI0_SCLK") (class "Default")
      (node (ref "R178") (pin "1") (pinfunction "1_1") (pintype "passive"))
      (node (ref "R185") (pin "2") (pinfunction "2_2") (pintype "passive"))
    )
    (net (code "19") (name "/RPI_SPI0_SCLK_R") (class "Default")
      (node (ref "IC33") (pin "6") (pinfunction "SCLK_6") (pintype "input"))
      (node (ref "IC36") (pin "2") (pinfunction "SCLK_2") (pintype "input"))
      (node (ref "R185") (pin "1") (pinfunction "1_1") (pintype "passive"))
    )
    (net (code "20") (name "/RPI_SPI0_SS0") (class "Default")
      (node (ref "R184") (pin "2") (pinfunction "2_2") (pintype "passive"))
    )
    (net (code "21") (name "/RPI_SPI0_SS0_R") (class "Default")
      (node (ref "IC33") (pin "5") (pinfunction "~{SYN}C_5") (pintype "input"))
      (node (ref "IC36") (pin "1") (pinfunction "~{SYNC}_1") (pintype "input"))
      (node (ref "R184") (pin "1") (pinfunction "1_1") (pintype "passive"))
    )
    (net (code "22") (name "/RPI_SPI0_SS1") (class "Default")
      (node (ref "R181") (pin "1") (pinfunction "1_1") (pintype "passive"))
    )
    (net (code "23") (name "/RPI_SYNC_IN") (class "Default")
      (node (ref "J38") (pin "2") (pinfunction "2_2") (pintype "passive"))
    )
    (net (code "24") (name "/RPI_SYNC_IN_LS") (class "Default")
      (node (ref "IC35") (pin "4") (pinfunction "HSD1-_4") (pintype "passive"))
      (node (ref "IC35") (pin "7") (pinfunction "HSD2+_7") (pintype "passive"))
      (node (ref "R173") (pin "1") (pinfunction "1_1") (pintype "passive"))
    )
    (net (code "25") (name "/RPI_SYNC_OUT") (class "Default")
      (node (ref "J34") (pin "5") (pinfunction "5_5") (pintype "passive"))
      (node (ref "J36") (pin "1") (pinfunction "1_1") (pintype "passive"))
      (node (ref "J37") (pin "1") (pinfunction "1_1") (pintype "passive"))
    )
    (net (code "26") (name "/RPI_SYNC_OUT_LS") (class "Default")
      (node (ref "IC35") (pin "5") (pinfunction "HSD1+_5") (pintype "passive"))
      (node (ref "R171") (pin "1") (pinfunction "1_1") (pintype "passive"))
    )
    (net (code "27") (name "/TCXO_DAC_VREF") (class "Default")
      (node (ref "C139") (pin "2") (pinfunction "2_2") (pintype "passive"))
      (node (ref "C140") (pin "1") (pinfunction "1_1") (pintype "passive"))
      (node (ref "IC33") (pin "2") (pinfunction "Vref_2") (pintype "input"))
      (node (ref "R165") (pin "1") (pinfunction "1_1") (pintype "passive"))
      (node (ref "R166") (pin "1") (pinfunction "1_1") (pintype "passive"))
      (node (ref "R172") (pin "1") (pinfunction "1_1") (pintype "passive"))
    )
    (net (code "28") (name "/XO_VC") (class "Default")
      (node (ref "R162") (pin "1") (pinfunction "1_1") (pintype "passive"))
      (node (ref "R167") (pin "2") (pinfunction "2_2") (pintype "passive"))
      (node (ref "XO1") (pin "1") (pinfunction "NC/VC_1") (pintype "passive"))
      (node (ref "XO2") (pin "1") (pinfunction "VC_1") (pintype "passive"))
      (node (ref "XO3") (pin "1") (pinfunction "Vc_1") (pintype "passive"))
      (node (ref "XO4") (pin "1") (pinfunction "VCO_1") (pintype "input"))
      (node (ref "XO5") (pin "1") (pinfunction "Vcon_1") (pintype "passive"))
    )
    (net (code "29") (name "GND") (class "Default")
      (node (ref "C102") (pin "1") (pinfunction "1_1") (pintype "passive"))
      (node (ref "C103") (pin "1") (pinfunction "1_1") (pintype "passive"))
      (node (ref "C104") (pin "1") (pinfunction "1_1") (pintype "passive"))
      (node (ref "C105") (pin "1") (pinfunction "1_1") (pintype "passive"))
      (node (ref "C106") (pin "1") (pinfunction "1_1") (pintype "passive"))
      (node (ref "C107") (pin "1") (pinfunction "1_1") (pintype "passive"))
      (node (ref "C108") (pin "1") (pinfunction "1_1") (pintype "passive"))
      (node (ref "C109") (pin "1") (pinfunction "1_1") (pintype "passive"))
      (node (ref "C110") (pin "1") (pinfunction "1_1") (pintype "passive"))
      (node (ref "C111") (pin "1") (pinfunction "1_1") (pintype "passive"))
      (node (ref "C112") (pin "1") (pinfunction "1_1") (pintype "passive"))
      (node (ref "C113") (pin "1") (pinfunction "1_1") (pintype "passive"))
      (node (ref "C114") (pin "1") (pinfunction "1_1") (pintype "passive"))
      (node (ref "C115") (pin "1") (pinfunction "1_1") (pintype "passive"))
      (node (ref "C116") (pin "1") (pinfunction "1_1") (pintype "passive"))
      (node (ref "C117") (pin "1") (pinfunction "1_1") (pintype "passive"))
      (node (ref "C118") (pin "1") (pinfunction "1_1") (pintype "passive"))
      (node (ref "C119") (pin "1") (pinfunction "1_1") (pintype "passive"))
      (node (ref "C120") (pin "1") (pinfunction "1_1") (pintype "passive"))
      (node (ref "C121") (pin "1") (pinfunction "1_1") (pintype "passive"))
      (node (ref "C122") (pin "1") (pinfunction "1_1") (pintype "passive"))
      (node (ref "C123") (pin "1") (pinfunction "1_1") (pintype "passive"))
      (node (ref "C124") (pin "2") (pinfunction "2_2") (pintype "passive"))
      (node (ref "C125") (pin "2") (pinfunction "2_2") (pintype "passive"))
      (node (ref "C128") (pin "1") (pinfunction "1_1") (pintype "passive"))
      (node (ref "C129") (pin "2") (pinfunction "2_2") (pintype "passive"))
      (node (ref "C130") (pin "2") (pinfunction "2_2") (pintype "passive"))
      (node (ref "C131") (pin "1") (pinfunction "1_1") (pintype "passive"))
      (node (ref "C132") (pin "2") (pinfunction "2_2") (pintype "passive"))
      (node (ref "C133") (pin "2") (pinfunction "2_2") (pintype "passive"))
      (node (ref "C134") (pin "1") (pinfunction "1_1") (pintype "passive"))
      (node (ref "C135") (pin "2") (pinfunction "2_2") (pintype "passive"))
      (node (ref "C136") (pin "2") (pinfunction "2_2") (pintype "passive"))
      (node (ref "C139") (pin "1") (pinfunction "1_1") (pintype "passive"))
      (node (ref "C140") (pin "2") (pinfunction "2_2") (pintype "passive"))
      (node (ref "C141") (pin "1") (pinfunction "1_1") (pintype "passive"))
      (node (ref "C143") (pin "1") (pinfunction "1_1") (pintype "passive"))
      (node (ref "C144") (pin "2") (pinfunction "2_2") (pintype "passive"))
      (node (ref "C145") (pin "2") (pinfunction "2_2") (pintype "passive"))
      (node (ref "C146") (pin "2") (pinfunction "2_2") (pintype "passive"))
      (node (ref "C147") (pin "2") (pinfunction "2_2") (pintype "passive"))
      (node (ref "C97") (pin "1") (pinfunction "1_1") (pintype "passive"))
      (node (ref "C98") (pin "1") (pinfunction "1_1") (pintype "passive"))
      (node (ref "C99") (pin "2") (pinfunction "2_2") (pintype "passive"))
      (node (ref "IC31") (pin "1") (pinfunction "GND_1") (pintype "passive"))
      (node (ref "IC31") (pin "11") (pinfunction "GND_11") (pintype "passive"))
      (node (ref "IC31") (pin "12") (pinfunction "GND_12") (pintype "passive"))
      (node (ref "IC31") (pin "16") (pinfunction "GND_16") (pintype "passive"))
      (node (ref "IC31") (pin "19") (pinfunction "GND_19") (pintype "passive"))
      (node (ref "IC31") (pin "22") (pinfunction "SEL_22") (pintype "passive"))
      (node (ref "IC31") (pin "25") (pinfunction "GND_25") (pintype "passive"))
      (node (ref "IC31") (pin "7") (pinfunction "GND_7") (pintype "passive"))
      (node (ref "IC32") (pin "2") (pinfunction "GND_2") (pintype "passive"))
      (node (ref "IC33") (pin "8") (pinfunction "GND_8") (pintype "passive"))
      (node (ref "IC34") (pin "1") (pinfunction "CPGND_1") (pintype "passive"))
      (node (ref "IC34") (pin "10") (pinfunction "DGND_10") (pintype "passive"))
      (node (ref "IC34") (pin "2") (pinfunction "AGND_2") (pintype "passive"))
      (node (ref "IC34") (pin "21") (pinfunction "AGND_21") (pintype "passive"))
      (node (ref "IC34") (pin "3") (pinfunction "AGND_3") (pintype "passive"))
      (node (ref "IC34") (pin "9") (pinfunction "DGND_9") (pintype "passive"))
      (node (ref "IC35") (pin "3") (pinfunction "GND_3") (pintype "passive"))
      (node (ref "IC35") (pin "8") (pinfunction "~{OE}_8") (pintype "input"))
      (node (ref "IC36") (pin "5") (pinfunction "GND_5") (pintype "power_in"))
      (node (ref "J32") (pin "2") (pinfunction "Y_2") (pintype "passive"))
      (node (ref "J33") (pin "2") (pinfunction "Y_2") (pintype "passive"))
      (node (ref "J35") (pin "2") (pinfunction "Y_2") (pintype "passive"))
      (node (ref "R149") (pin "1") (pinfunction "1_1") (pintype "passive"))
      (node (ref "R163") (pin "1") (pinfunction "1_1") (pintype "passive"))
      (node (ref "R170") (pin "1") (pinfunction "1_1") (pintype "passive"))
      (node (ref "R172") (pin "2") (pinfunction "2_2") (pintype "passive"))
      (node (ref "R174") (pin "2") (pinfunction "2_2") (pintype "passive"))
      (node (ref "R175") (pin "2") (pinfunction "2_2") (pintype "passive"))
      (node (ref "R176") (pin "1") (pinfunction "1_1") (pintype "passive"))
      (node (ref "R182") (pin "2") (pinfunction "2_2") (pintype "passive"))
      (node (ref "R183") (pin "2") (pinfunction "2_2") (pintype "passive"))
      (node (ref "XO1") (pin "2") (pinfunction "GND_2") (pintype "passive"))
      (node (ref "XO2") (pin "2") (pinfunction "GND_2") (pintype "passive"))
      (node (ref "XO3") (pin "2") (pinfunction "GND_2") (pintype "passive"))
      (node (ref "XO4") (pin "4") (pinfunction "GND_4") (pintype "passive"))
      (node (ref "XO5") (pin "2") (pinfunction "GND_2") (pintype "passive"))
    )
    (net (code "30") (name "Net-(C100-Pad2)") (class "Default")
      (node (ref "C100") (pin "2") (pinfunction "2_2") (pintype "passive"))
      (node (ref "C101") (pin "1") (pinfunction "1_1") (pintype "passive"))
      (node (ref "R149") (pin "2") (pinfunction "2_2") (pintype "passive"))
    )
    (net (code "31") (name "Net-(C101-Pad2)") (class "Default")
      (node (ref "C101") (pin "2") (pinfunction "2_2") (pintype "passive"))
      (node (ref "R145") (pin "1") (pinfunction "1_1") (pintype "passive"))
      (node (ref "R151") (pin "1") (pinfunction "1_1") (pintype "passive"))
      (node (ref "R155") (pin "2") (pinfunction "2_2") (pintype "passive"))
      (node (ref "R158") (pin "1") (pinfunction "1_1") (pintype "passive"))
    )
    (net (code "32") (name "Net-(C123-Pad2)") (class "Default")
      (node (ref "C123") (pin "2") (pinfunction "2_2") (pintype "passive"))
      (node (ref "C124") (pin "1") (pinfunction "1_1") (pintype "passive"))
      (node (ref "C125") (pin "1") (pinfunction "1_1") (pintype "passive"))
      (node (ref "FR7") (pin "2") (pinfunction "2_2") (pintype "passive"))
      (node (ref "IC34") (pin "6") (pinfunction "AVdd_6") (pintype "passive"))
      (node (ref "IC34") (pin "7") (pinfunction "AVdd_7") (pintype "passive"))
    )
    (net (code "33") (name "Net-(C126-Pad2)") (class "Default")
      (node (ref "C126") (pin "2") (pinfunction "2_2") (pintype "passive"))
      (node (ref "C127") (pin "1") (pinfunction "1_1") (pintype "passive"))
      (node (ref "R163") (pin "2") (pinfunction "2_2") (pintype "passive"))
    )
    (net (code "34") (name "Net-(C131-Pad2)") (class "Default")
      (node (ref "C131") (pin "2") (pinfunction "2_2") (pintype "passive"))
      (node (ref "R161") (pin "1") (pinfunction "1_1") (pintype "passive"))
      (node (ref "R162") (pin "2") (pinfunction "2_2") (pintype "passive"))
      (node (ref "R177") (pin "2") (pinfunction "2_2") (pintype "passive"))
      (node (ref "R179") (pin "1") (pinfunction "1_1") (pintype "passive"))
      (node (ref "R182") (pin "1") (pinfunction "1_1") (pintype "passive"))
    )
    (net (code "35") (name "Net-(C137-Pad2)") (class "Default")
      (node (ref "C137") (pin "2") (pinfunction "2_2") (pintype "passive"))
      (node (ref "C138") (pin "1") (pinfunction "1_1") (pintype "passive"))
      (node (ref "R170") (pin "2") (pinfunction "2_2") (pintype "passive"))
    )
    (net (code "36") (name "Net-(C141-Pad2)") (class "Default")
      (node (ref "C141") (pin "2") (pinfunction "2_2") (pintype "passive"))
      (node (ref "R167") (pin "1") (pinfunction "1_1") (pintype "passive"))
      (node (ref "R169") (pin "2") (pinfunction "2_2") (pintype "passive"))
    )
    (net (code "37") (name "Net-(C142-Pad1)") (class "Default")
      (node (ref "C142") (pin "1") (pinfunction "1_1") (pintype "passive"))
      (node (ref "R176") (pin "2") (pinfunction "2_2") (pintype "passive"))
    )
    (net (code "38") (name "Net-(FR4-Pad2)") (class "Default")
      (node (ref "FR4") (pin "2") (pinfunction "2_2") (pintype "passive"))
      (node (ref "R146") (pin "1") (pinfunction "1_1") (pintype "passive"))
      (node (ref "R152") (pin "2") (pinfunction "2_2") (pintype "passive"))
      (node (ref "R154") (pin "1") (pinfunction "1_1") (pintype "passive"))
      (node (ref "R157") (pin "1") (pinfunction "1_1") (pintype "passive"))
    )
    (net (code "39") (name "Net-(IC31-CLKin)") (class "Default")
      (node (ref "C100") (pin "1") (pinfunction "1_1") (pintype "passive"))
      (node (ref "IC31") (pin "21") (pinfunction "CLKin_21") (pintype "passive"))
    )
    (net (code "40") (name "Net-(IC31-CLKin*)") (class "Default")
      (node (ref "C102") (pin "2") (pinfunction "2_2") (pintype "passive"))
      (node (ref "IC31") (pin "20") (pinfunction "CLKin*_20") (pintype "passive"))
    )
    (net (code "41") (name "Net-(IC31-OE)") (class "Default")
      (node (ref "IC31") (pin "24") (pinfunction "OE_24") (pintype "passive"))
      (node (ref "R147") (pin "1") (pinfunction "1_1") (pintype "passive"))
    )
    (net (code "42") (name "Net-(IC32-EN)") (class "Default")
      (node (ref "C118") (pin "2") (pinfunction "2_2") (pintype "passive"))
      (node (ref "C120") (pin "2") (pinfunction "2_2") (pintype "passive"))
      (node (ref "IC32") (pin "1") (pinfunction "IN_1") (pintype "input"))
      (node (ref "IC32") (pin "3") (pinfunction "EN_3") (pintype "input"))
      (node (ref "R157") (pin "2") (pinfunction "2_2") (pintype "passive"))
      (node (ref "R159") (pin "2") (pinfunction "2_2") (pintype "passive"))
    )
    (net (code "43") (name "Net-(IC32-OUT)") (class "Default")
      (node (ref "C119") (pin "2") (pinfunction "2_2") (pintype "passive"))
      (node (ref "C121") (pin "2") (pinfunction "2_2") (pintype "passive"))
      (node (ref "IC32") (pin "5") (pinfunction "OUT_5") (pintype "output"))
      (node (ref "R159") (pin "1") (pinfunction "1_1") (pintype "passive"))
      (node (ref "XO5") (pin "4") (pinfunction "VCC_4") (pintype "passive"))
    )
    (net (code "44") (name "Net-(IC33-Vdd)") (class "Default")
      (node (ref "C128") (pin "2") (pinfunction "2_2") (pintype "passive"))
      (node (ref "C129") (pin "1") (pinfunction "1_1") (pintype "passive"))
      (node (ref "C130") (pin "1") (pinfunction "1_1") (pintype "passive"))
      (node (ref "C146") (pin "1") (pinfunction "1_1") (pintype "passive"))
      (node (ref "FR8") (pin "1") (pinfunction "1_1") (pintype "passive"))
      (node (ref "IC33") (pin "1") (pinfunction "Vdd_1") (pintype "power_in"))
      (node (ref "IC36") (pin "4") (pinfunction "VDD_4") (pintype "power_in"))
      (node (ref "R166") (pin "2") (pinfunction "2_2") (pintype "passive"))
    )
    (net (code "45") (name "Net-(IC33-Vfb)") (class "Default")
      (node (ref "C135") (pin "1") (pinfunction "1_1") (pintype "passive"))
      (node (ref "IC33") (pin "3") (pinfunction "Vfb_3") (pintype "input"))
      (node (ref "IC33") (pin "4") (pinfunction "Vout_4") (pintype "output"))
      (node (ref "R161") (pin "2") (pinfunction "2_2") (pintype "passive"))
    )
    (net (code "46") (name "Net-(IC34-CE)") (class "Default")
      (node (ref "IC34") (pin "11") (pinfunction "CE_11") (pintype "passive"))
      (node (ref "R168") (pin "1") (pinfunction "1_1") (pintype "passive"))
    )
    (net (code "47") (name "Net-(IC34-CLK)") (class "Default")
      (node (ref "C145") (pin "1") (pinfunction "1_1") (pintype "passive"))
      (node (ref "IC34") (pin "12") (pinfunction "CLK_12") (pintype "passive"))
      (node (ref "R178") (pin "2") (pinfunction "2_2") (pintype "passive"))
    )
    (net (code "48") (name "Net-(IC34-CP)") (class "Default")
      (node (ref "C142") (pin "2") (pinfunction "2_2") (pintype "passive"))
      (node (ref "C143") (pin "2") (pinfunction "2_2") (pintype "passive"))
      (node (ref "IC34") (pin "20") (pinfunction "CP_20") (pintype "passive"))
      (node (ref "R169") (pin "1") (pinfunction "1_1") (pintype "passive"))
    )
    (net (code "49") (name "Net-(IC34-DATA)") (class "Default")
      (node (ref "IC34") (pin "13") (pinfunction "DATA_13") (pintype "passive"))
      (node (ref "R180") (pin "2") (pinfunction "2_2") (pintype "passive"))
    )
    (net (code "50") (name "Net-(IC34-LE)") (class "Default")
      (node (ref "IC34") (pin "14") (pinfunction "LE_14") (pintype "passive"))
      (node (ref "R181") (pin "2") (pinfunction "2_2") (pintype "passive"))
    )
    (net (code "51") (name "Net-(IC34-REFin)") (class "Default")
      (node (ref "C137") (pin "1") (pinfunction "1_1") (pintype "passive"))
      (node (ref "IC34") (pin "8") (pinfunction "REFin_8") (pintype "passive"))
    )
    (net (code "52") (name "Net-(IC34-RFinA)") (class "Default")
      (node (ref "C126") (pin "1") (pinfunction "1_1") (pintype "passive"))
      (node (ref "IC34") (pin "5") (pinfunction "RFinA_5") (pintype "passive"))
    )
    (net (code "53") (name "Net-(IC34-RFinB)") (class "Default")
      (node (ref "C144") (pin "1") (pinfunction "1_1") (pintype "passive"))
      (node (ref "IC34") (pin "4") (pinfunction "RFinB_4") (pintype "passive"))
    )
    (net (code "54") (name "Net-(IC34-Rset)") (class "Default")
      (node (ref "IC34") (pin "19") (pinfunction "Rset_19") (pintype "passive"))
      (node (ref "R175") (pin "1") (pinfunction "1_1") (pintype "passive"))
    )
    (net (code "55") (name "Net-(IC34-Vp)") (class "Default")
      (node (ref "C134") (pin "2") (pinfunction "2_2") (pintype "passive"))
      (node (ref "C136") (pin "1") (pinfunction "1_1") (pintype "passive"))
      (node (ref "IC34") (pin "18") (pinfunction "Vp_18") (pintype "passive"))
      (node (ref "R164") (pin "1") (pinfunction "1_1") (pintype "passive"))
    )
    (net (code "56") (name "Net-(IC36-VOUT)") (class "Default")
      (node (ref "IC36") (pin "6") (pinfunction "VOUT_6") (pintype "tri_state"))
      (node (ref "R179") (pin "2") (pinfunction "2_2") (pintype "passive"))
    )
    (net (code "57") (name "Net-(J33-X)") (class "Default")
      (node (ref "J33") (pin "1") (pinfunction "X_1") (pintype "passive"))
      (node (ref "R148") (pin "1") (pinfunction "1_1") (pintype "passive"))
    )
    (net (code "58") (name "Net-(J37-Pad2)") (class "Default")
      (node (ref "J37") (pin "2") (pinfunction "2_2") (pintype "passive"))
      (node (ref "R153") (pin "1") (pinfunction "1_1") (pintype "passive"))
    )
    (net (code "59") (name "Net-(R154-Pad2)") (class "Default")
      (node (ref "R154") (pin "2") (pinfunction "2_2") (pintype "passive"))
      (node (ref "R156") (pin "1") (pinfunction "1_1") (pintype "passive"))
    )
    (net (code "60") (name "Net-(XO1-Output)") (class "Default")
      (node (ref "R145") (pin "2") (pinfunction "2_2") (pintype "passive"))
      (node (ref "XO1") (pin "3") (pinfunction "Output_3") (pintype "output"))
    )
    (net (code "61") (name "Net-(XO1-Vcc)") (class "Default")
      (node (ref "C97") (pin "2") (pinfunction "2_2") (pintype "passive"))
      (node (ref "C98") (pin "2") (pinfunction "2_2") (pintype "passive"))
      (node (ref "C99") (pin "1") (pinfunction "1_1") (pintype "passive"))
      (node (ref "R146") (pin "2") (pinfunction "2_2") (pintype "passive"))
      (node (ref "XO1") (pin "4") (pinfunction "Vcc_4") (pintype "power_in"))
    )
    (net (code "62") (name "Net-(XO2-OUT)") (class "Default")
      (node (ref "R151") (pin "2") (pinfunction "2_2") (pintype "passive"))
      (node (ref "XO2") (pin "4") (pinfunction "OUT_4") (pintype "passive"))
      (node (ref "XO3") (pin "3") (pinfunction "OUT_3") (pintype "passive"))
    )
    (net (code "63") (name "Net-(XO2-TRI-ST.)") (class "Default")
      (node (ref "R150") (pin "1") (pinfunction "1_1") (pintype "passive"))
      (node (ref "XO2") (pin "6") (pinfunction "TRI-ST._6") (pintype "passive"))
    )
    (net (code "64") (name "Net-(XO2-VDD)") (class "Default")
      (node (ref "C103") (pin "2") (pinfunction "2_2") (pintype "passive"))
      (node (ref "C104") (pin "2") (pinfunction "2_2") (pintype "passive"))
      (node (ref "R150") (pin "2") (pinfunction "2_2") (pintype "passive"))
      (node (ref "R152") (pin "1") (pinfunction "1_1") (pintype "passive"))
      (node (ref "XO2") (pin "5") (pinfunction "VDD_5") (pintype "passive"))
      (node (ref "XO3") (pin "4") (pinfunction "VDD_4") (pintype "passive"))
    )
    (net (code "65") (name "Net-(XO4-RF_OUT)") (class "Default")
      (node (ref "R155") (pin "1") (pinfunction "1_1") (pintype "passive"))
      (node (ref "XO4") (pin "6") (pinfunction "RF_OUT_6") (pintype "output"))
    )
    (net (code "66") (name "Net-(XO4-VCC)") (class "Default")
      (node (ref "C109") (pin "2") (pinfunction "2_2") (pintype "passive"))
      (node (ref "C110") (pin "2") (pinfunction "2_2") (pintype "passive"))
      (node (ref "R156") (pin "2") (pinfunction "2_2") (pintype "passive"))
      (node (ref "XO4") (pin "9") (pinfunction "VCC_9") (pintype "power_in"))
    )
    (net (code "67") (name "Net-(XO4-VC_FILTER)") (class "Default")
      (node (ref "C111") (pin "2") (pinfunction "2_2") (pintype "passive"))
      (node (ref "XO4") (pin "7") (pinfunction "VC_FILTER_7") (pintype "input"))
    )
    (net (code "68") (name "Net-(XO5-OUT)") (class "Default")
      (node (ref "R158") (pin "2") (pinfunction "2_2") (pintype "passive"))
      (node (ref "R160") (pin "1") (pinfunction "1_1") (pintype "passive"))
      (node (ref "XO5") (pin "3") (pinfunction "OUT_3") (pintype "passive"))
    )
    (net (code "69") (name "VCC2P5_VREF") (class "Default")
      (node (ref "R165") (pin "2") (pinfunction "2_2") (pintype "passive"))
    )
    (net (code "70") (name "VCC3P3") (class "Default")
      (node (ref "C147") (pin "1") (pinfunction "1_1") (pintype "passive"))
      (node (ref "IC35") (pin "9") (pinfunction "VCC_9") (pintype "power_in"))
    )
    (net (code "71") (name "VCC3P3_CLK") (class "Default")
      (node (ref "C122") (pin "2") (pinfunction "2_2") (pintype "passive"))
      (node (ref "C132") (pin "1") (pinfunction "1_1") (pintype "passive"))
      (node (ref "C133") (pin "1") (pinfunction "1_1") (pintype "passive"))
      (node (ref "FR4") (pin "1") (pinfunction "1_1") (pintype "passive"))
      (node (ref "FR5") (pin "1") (pinfunction "1_1") (pintype "passive"))
      (node (ref "FR6") (pin "1") (pinfunction "1_1") (pintype "passive"))
      (node (ref "FR7") (pin "1") (pinfunction "1_1") (pintype "passive"))
      (node (ref "FR8") (pin "2") (pinfunction "2_2") (pintype "passive"))
      (node (ref "IC34") (pin "16") (pinfunction "DVdd_16") (pintype "passive"))
      (node (ref "IC34") (pin "17") (pinfunction "DVdd_17") (pintype "passive"))
      (node (ref "R164") (pin "2") (pinfunction "2_2") (pintype "passive"))
      (node (ref "R168") (pin "2") (pinfunction "2_2") (pintype "passive"))
      (node (ref "R177") (pin "1") (pinfunction "1_1") (pintype "passive"))
    )
    (net (code "72") (name "VCC3P3_LMK") (class "Default")
      (node (ref "C105") (pin "2") (pinfunction "2_2") (pintype "passive"))
      (node (ref "C106") (pin "2") (pinfunction "2_2") (pintype "passive"))
      (node (ref "C107") (pin "2") (pinfunction "2_2") (pintype "passive"))
      (node (ref "C108") (pin "2") (pinfunction "2_2") (pintype "passive"))
      (node (ref "FR5") (pin "2") (pinfunction "2_2") (pintype "passive"))
      (node (ref "IC31") (pin "23") (pinfunction "Vdd_23") (pintype "passive"))
      (node (ref "IC31") (pin "8") (pinfunction "Vdd_8") (pintype "passive"))
      (node (ref "R147") (pin "2") (pinfunction "2_2") (pintype "passive"))
    )
    (net (code "73") (name "VCC3P3_LMK_VDDO") (class "Default")
      (node (ref "C112") (pin "2") (pinfunction "2_2") (pintype "passive"))
      (node (ref "C113") (pin "2") (pinfunction "2_2") (pintype "passive"))
      (node (ref "C114") (pin "2") (pinfunction "2_2") (pintype "passive"))
      (node (ref "C115") (pin "2") (pinfunction "2_2") (pintype "passive"))
      (node (ref "C116") (pin "2") (pinfunction "2_2") (pintype "passive"))
      (node (ref "C117") (pin "2") (pinfunction "2_2") (pintype "passive"))
      (node (ref "FR6") (pin "2") (pinfunction "2_2") (pintype "passive"))
      (node (ref "IC31") (pin "14") (pinfunction "Vddo_14") (pintype "passive"))
      (node (ref "IC31") (pin "18") (pinfunction "Vddo_18") (pintype "passive"))
      (node (ref "IC31") (pin "2") (pinfunction "Vddo_2") (pintype "passive"))
      (node (ref "IC31") (pin "6") (pinfunction "Vddo_6") (pintype "passive"))
    )
    (net (code "74") (name "unconnected-(IC31-CLKout4-Pad17)") (class "Default")
      (node (ref "IC31") (pin "17") (pinfunction "CLKout4_17") (pintype "passive+no_connect"))
    )
    (net (code "75") (name "unconnected-(IC31-OSCin-Pad9)") (class "Default")
      (node (ref "IC31") (pin "9") (pinfunction "OSCin_9") (pintype "passive+no_connect"))
    )
    (net (code "76") (name "unconnected-(IC31-OSCout-Pad10)") (class "Default")
      (node (ref "IC31") (pin "10") (pinfunction "OSCout_10") (pintype "passive+no_connect"))
    )
    (net (code "77") (name "unconnected-(IC32-NC-Pad4)") (class "Default")
      (node (ref "IC32") (pin "4") (pinfunction "NC_4") (pintype "passive+no_connect"))
    )
    (net (code "78") (name "unconnected-(IC35-HSD2--Pad6)") (class "Default")
      (node (ref "IC35") (pin "6") (pinfunction "HSD2-_6") (pintype "passive+no_connect"))
    )
    (net (code "79") (name "unconnected-(JMP2-Pad1)") (class "Default")
      (node (ref "JMP2") (pin "1") (pinfunction "1_1") (pintype "passive"))
    )
    (net (code "80") (name "unconnected-(JMP2-Pad2)") (class "Default")
      (node (ref "JMP2") (pin "2") (pinfunction "2_2") (pintype "passive"))
    )
    (net (code "81") (name "unconnected-(JMP3-Pad1)") (class "Default")
      (node (ref "JMP3") (pin "1") (pinfunction "1_1") (pintype "passive"))
    )
    (net (code "82") (name "unconnected-(JMP3-Pad2)") (class "Default")
      (node (ref "JMP3") (pin "2") (pinfunction "2_2") (pintype "passive"))
    )
    (net (code "83") (name "unconnected-(JMP4-Pad1)") (class "Default")
      (node (ref "JMP4") (pin "1") (pinfunction "1_1") (pintype "passive"))
    )
    (net (code "84") (name "unconnected-(JMP4-Pad2)") (class "Default")
      (node (ref "JMP4") (pin "2") (pinfunction "2_2") (pintype "passive"))
    )
    (net (code "85") (name "unconnected-(JMP5-Pad1)") (class "Default")
      (node (ref "JMP5") (pin "1") (pinfunction "1_1") (pintype "passive"))
    )
    (net (code "86") (name "unconnected-(JMP5-Pad2)") (class "Default")
      (node (ref "JMP5") (pin "2") (pinfunction "2_2") (pintype "passive"))
    )
    (net (code "87") (name "unconnected-(JMP6-Pad1)") (class "Default")
      (node (ref "JMP6") (pin "1") (pinfunction "1_1") (pintype "passive"))
    )
    (net (code "88") (name "unconnected-(JMP6-Pad2)") (class "Default")
      (node (ref "JMP6") (pin "2") (pinfunction "2_2") (pintype "passive"))
    )
    (net (code "89") (name "unconnected-(XO2-T.S.-Pad3)") (class "Default")
      (node (ref "XO2") (pin "3") (pinfunction "T.S._3") (pintype "passive+no_connect"))
    )
    (net (code "90") (name "unconnected-(XO4-NC-Pad2)") (class "Default")
      (node (ref "XO4") (pin "2") (pinfunction "NC_2") (pintype "passive+no_connect"))
    )
    (net (code "91") (name "unconnected-(XO4-NC-Pad3)") (class "Default")
      (node (ref "XO4") (pin "3") (pinfunction "NC_3") (pintype "passive+no_connect"))
    )
    (net (code "92") (name "unconnected-(XO4-NC-Pad5)") (class "Default")
      (node (ref "XO4") (pin "5") (pinfunction "NC_5") (pintype "passive+no_connect"))
    )
    (net (code "93") (name "unconnected-(XO4-NC-Pad8)") (class "Default")
      (node (ref "XO4") (pin "8") (pinfunction "NC_8") (pintype "passive+no_connect"))
    )
    (net (code "94") (name "unconnected-(XO4-NC-Pad10)") (class "Default")
      (node (ref "XO4") (pin "10") (pinfunction "NC_10") (pintype "passive+no_connect"))
    )
  )
)
